# Connectors.net
KiCad netlist of a schematic drawn in Altium Designer
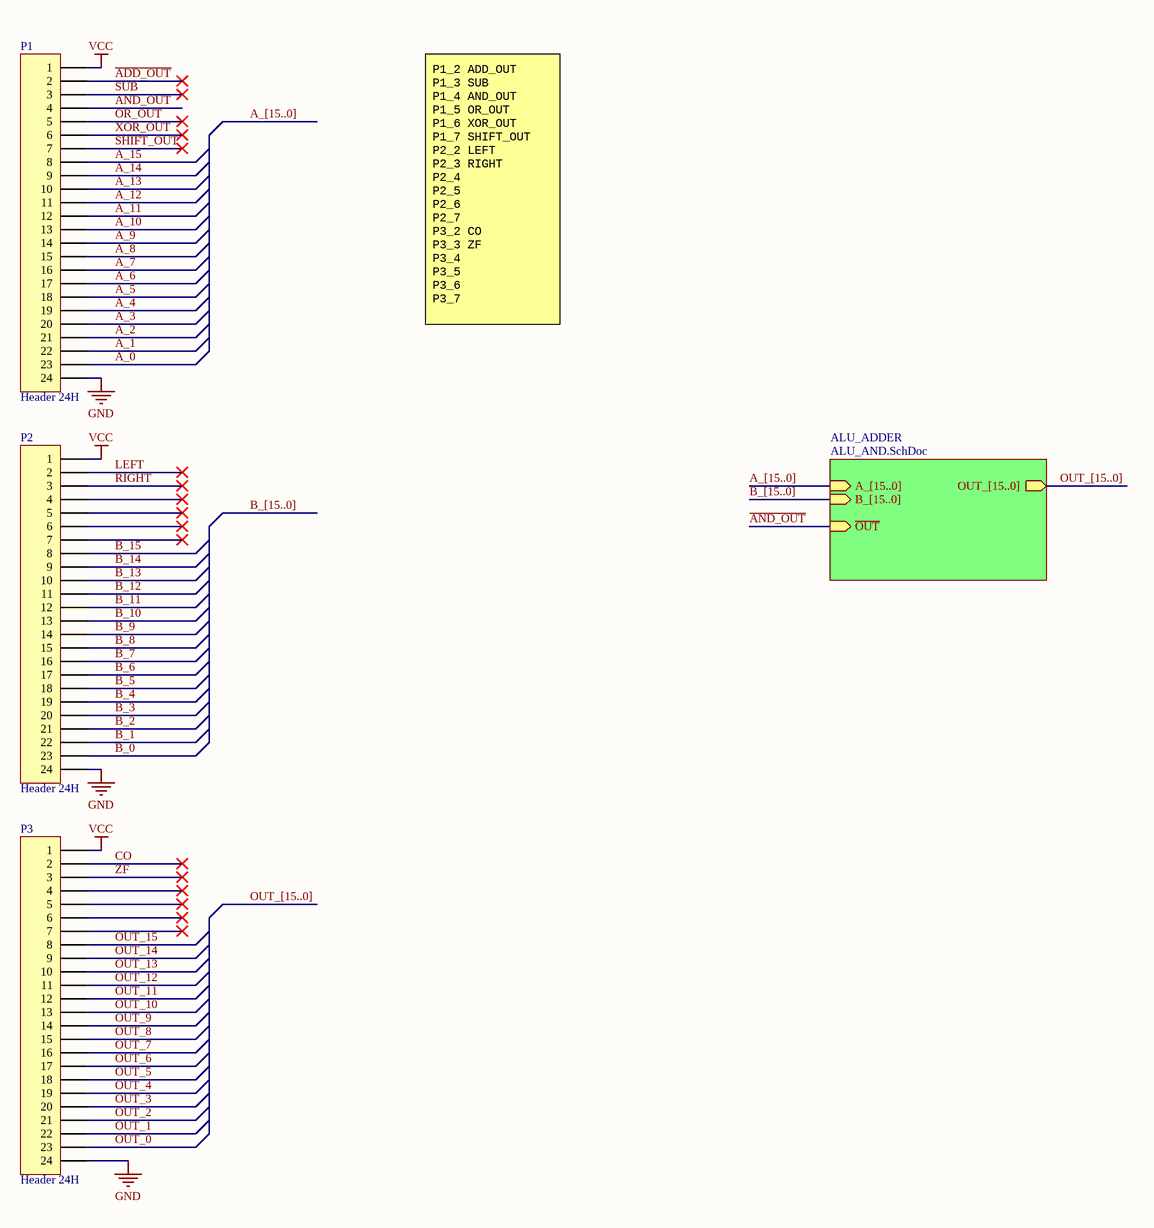
[diagram p0: Connectors.SchDoc]

(export (version "E")
  (design (tool "Eeschema 10.0.6"))
  (components
    (comp (ref "P1")
      (value "Header 24H")
      (footprint "HDR1X24H")
      (description "Header, 24-Pin, Right Angle")
      (fields (field (name "PUBLISHER") "Altium Limited"))
      (libsource (lib "Miscellaneous Connectors") (part "Header 24H"))
    )
    (comp (ref "P2")
      (value "Header 24H")
      (footprint "HDR1X24H")
      (description "Header, 24-Pin, Right Angle")
      (fields (field (name "PUBLISHER") "Altium Limited"))
      (libsource (lib "Miscellaneous Connectors") (part "Header 24H"))
    )
    (comp (ref "P3")
      (value "Header 24H")
      (footprint "HDR1X24H")
      (description "Header, 24-Pin, Right Angle")
      (fields (field (name "PUBLISHER") "Altium Limited"))
      (libsource (lib "Miscellaneous Connectors") (part "Header 24H"))
    )
  )
  (nets
    (net (code "1") (name "/A_0") (class "Default")
      (node (ref "P1") (pin "23") (pinfunction "23_23") (pintype "passive"))
    )
    (net (code "2") (name "/A_1") (class "Default")
      (node (ref "P1") (pin "22") (pinfunction "22_22") (pintype "passive"))
    )
    (net (code "3") (name "/A_2") (class "Default")
      (node (ref "P1") (pin "21") (pinfunction "21_21") (pintype "passive"))
    )
    (net (code "4") (name "/A_3") (class "Default")
      (node (ref "P1") (pin "20") (pinfunction "20_20") (pintype "passive"))
    )
    (net (code "5") (name "/A_4") (class "Default")
      (node (ref "P1") (pin "19") (pinfunction "19_19") (pintype "passive"))
    )
    (net (code "6") (name "/A_5") (class "Default")
      (node (ref "P1") (pin "18") (pinfunction "18_18") (pintype "passive"))
    )
    (net (code "7") (name "/A_6") (class "Default")
      (node (ref "P1") (pin "17") (pinfunction "17_17") (pintype "passive"))
    )
    (net (code "8") (name "/A_7") (class "Default")
      (node (ref "P1") (pin "16") (pinfunction "16_16") (pintype "passive"))
    )
    (net (code "9") (name "/A_8") (class "Default")
      (node (ref "P1") (pin "15") (pinfunction "15_15") (pintype "passive"))
    )
    (net (code "10") (name "/A_9") (class "Default")
      (node (ref "P1") (pin "14") (pinfunction "14_14") (pintype "passive"))
    )
    (net (code "11") (name "/A_10") (class "Default")
      (node (ref "P1") (pin "13") (pinfunction "13_13") (pintype "passive"))
    )
    (net (code "12") (name "/A_11") (class "Default")
      (node (ref "P1") (pin "12") (pinfunction "12_12") (pintype "passive"))
    )
    (net (code "13") (name "/A_12") (class "Default")
      (node (ref "P1") (pin "11") (pinfunction "11_11") (pintype "passive"))
    )
    (net (code "14") (name "/A_13") (class "Default")
      (node (ref "P1") (pin "10") (pinfunction "10_10") (pintype "passive"))
    )
    (net (code "15") (name "/A_14") (class "Default")
      (node (ref "P1") (pin "9") (pinfunction "9_9") (pintype "passive"))
    )
    (net (code "16") (name "/A_15") (class "Default")
      (node (ref "P1") (pin "8") (pinfunction "8_8") (pintype "passive"))
    )
    (net (code "18") (name "/B_0") (class "Default")
      (node (ref "P2") (pin "23") (pinfunction "23_23") (pintype "passive"))
    )
    (net (code "19") (name "/B_1") (class "Default")
      (node (ref "P2") (pin "22") (pinfunction "22_22") (pintype "passive"))
    )
    (net (code "20") (name "/B_2") (class "Default")
      (node (ref "P2") (pin "21") (pinfunction "21_21") (pintype "passive"))
    )
    (net (code "21") (name "/B_3") (class "Default")
      (node (ref "P2") (pin "20") (pinfunction "20_20") (pintype "passive"))
    )
    (net (code "22") (name "/B_4") (class "Default")
      (node (ref "P2") (pin "19") (pinfunction "19_19") (pintype "passive"))
    )
    (net (code "23") (name "/B_5") (class "Default")
      (node (ref "P2") (pin "18") (pinfunction "18_18") (pintype "passive"))
    )
    (net (code "24") (name "/B_6") (class "Default")
      (node (ref "P2") (pin "17") (pinfunction "17_17") (pintype "passive"))
    )
    (net (code "25") (name "/B_7") (class "Default")
      (node (ref "P2") (pin "16") (pinfunction "16_16") (pintype "passive"))
    )
    (net (code "26") (name "/B_8") (class "Default")
      (node (ref "P2") (pin "15") (pinfunction "15_15") (pintype "passive"))
    )
    (net (code "27") (name "/B_9") (class "Default")
      (node (ref "P2") (pin "14") (pinfunction "14_14") (pintype "passive"))
    )
    (net (code "28") (name "/B_10") (class "Default")
      (node (ref "P2") (pin "13") (pinfunction "13_13") (pintype "passive"))
    )
    (net (code "29") (name "/B_11") (class "Default")
      (node (ref "P2") (pin "12") (pinfunction "12_12") (pintype "passive"))
    )
    (net (code "30") (name "/B_12") (class "Default")
      (node (ref "P2") (pin "11") (pinfunction "11_11") (pintype "passive"))
    )
    (net (code "31") (name "/B_13") (class "Default")
      (node (ref "P2") (pin "10") (pinfunction "10_10") (pintype "passive"))
    )
    (net (code "32") (name "/B_14") (class "Default")
      (node (ref "P2") (pin "9") (pinfunction "9_9") (pintype "passive"))
    )
    (net (code "33") (name "/B_15") (class "Default")
      (node (ref "P2") (pin "8") (pinfunction "8_8") (pintype "passive"))
    )
    (net (code "35") (name "/CO") (class "Default")
      (node (ref "P3") (pin "2") (pinfunction "2_2") (pintype "passive+no_connect"))
    )
    (net (code "36") (name "/LEFT") (class "Default")
      (node (ref "P2") (pin "2") (pinfunction "2_2") (pintype "passive+no_connect"))
    )
    (net (code "37") (name "/OUT_0") (class "Default")
      (node (ref "P3") (pin "23") (pinfunction "23_23") (pintype "passive"))
    )
    (net (code "38") (name "/OUT_1") (class "Default")
      (node (ref "P3") (pin "22") (pinfunction "22_22") (pintype "passive"))
    )
    (net (code "39") (name "/OUT_2") (class "Default")
      (node (ref "P3") (pin "21") (pinfunction "21_21") (pintype "passive"))
    )
    (net (code "40") (name "/OUT_3") (class "Default")
      (node (ref "P3") (pin "20") (pinfunction "20_20") (pintype "passive"))
    )
    (net (code "41") (name "/OUT_4") (class "Default")
      (node (ref "P3") (pin "19") (pinfunction "19_19") (pintype "passive"))
    )
    (net (code "42") (name "/OUT_5") (class "Default")
      (node (ref "P3") (pin "18") (pinfunction "18_18") (pintype "passive"))
    )
    (net (code "43") (name "/OUT_6") (class "Default")
      (node (ref "P3") (pin "17") (pinfunction "17_17") (pintype "passive"))
    )
    (net (code "44") (name "/OUT_7") (class "Default")
      (node (ref "P3") (pin "16") (pinfunction "16_16") (pintype "passive"))
    )
    (net (code "45") (name "/OUT_8") (class "Default")
      (node (ref "P3") (pin "15") (pinfunction "15_15") (pintype "passive"))
    )
    (net (code "46") (name "/OUT_9") (class "Default")
      (node (ref "P3") (pin "14") (pinfunction "14_14") (pintype "passive"))
    )
    (net (code "47") (name "/OUT_10") (class "Default")
      (node (ref "P3") (pin "13") (pinfunction "13_13") (pintype "passive"))
    )
    (net (code "48") (name "/OUT_11") (class "Default")
      (node (ref "P3") (pin "12") (pinfunction "12_12") (pintype "passive"))
    )
    (net (code "49") (name "/OUT_12") (class "Default")
      (node (ref "P3") (pin "11") (pinfunction "11_11") (pintype "passive"))
    )
    (net (code "50") (name "/OUT_13") (class "Default")
      (node (ref "P3") (pin "10") (pinfunction "10_10") (pintype "passive"))
    )
    (net (code "51") (name "/OUT_14") (class "Default")
      (node (ref "P3") (pin "9") (pinfunction "9_9") (pintype "passive"))
    )
    (net (code "52") (name "/OUT_15") (class "Default")
      (node (ref "P3") (pin "8") (pinfunction "8_8") (pintype "passive"))
    )
    (net (code "54") (name "/RIGHT") (class "Default")
      (node (ref "P2") (pin "3") (pinfunction "3_3") (pintype "passive+no_connect"))
    )
    (net (code "55") (name "/SUB") (class "Default")
      (node (ref "P1") (pin "3") (pinfunction "3_3") (pintype "passive+no_connect"))
    )
    (net (code "56") (name "/~{ADD_OUT}") (class "Default")
      (node (ref "P1") (pin "2") (pinfunction "2_2") (pintype "passive+no_connect"))
    )
    (net (code "57") (name "/~{AND_OUT}") (class "Default")
      (node (ref "P1") (pin "4") (pinfunction "4_4") (pintype "passive"))
    )
    (net (code "58") (name "/~{OR_OUT}") (class "Default")
      (node (ref "P1") (pin "5") (pinfunction "5_5") (pintype "passive+no_connect"))
    )
    (net (code "59") (name "/~{SHIFT_OUT}") (class "Default")
      (node (ref "P1") (pin "7") (pinfunction "7_7") (pintype "passive+no_connect"))
    )
    (net (code "60") (name "/~{XOR_OUT}") (class "Default")
      (node (ref "P1") (pin "6") (pinfunction "6_6") (pintype "passive+no_connect"))
    )
    (net (code "61") (name "/~{ZF}") (class "Default")
      (node (ref "P3") (pin "3") (pinfunction "3_3") (pintype "passive+no_connect"))
    )
    (net (code "62") (name "GND") (class "Default")
      (node (ref "P1") (pin "24") (pinfunction "24_24") (pintype "passive"))
      (node (ref "P2") (pin "24") (pinfunction "24_24") (pintype "passive"))
      (node (ref "P3") (pin "24") (pinfunction "24_24") (pintype "passive"))
    )
    (net (code "63") (name "VCC") (class "Default")
      (node (ref "P1") (pin "1") (pinfunction "1_1") (pintype "passive"))
      (node (ref "P2") (pin "1") (pinfunction "1_1") (pintype "passive"))
      (node (ref "P3") (pin "1") (pinfunction "1_1") (pintype "passive"))
    )
    (net (code "64") (name "unconnected-(P2-Pad4)") (class "Default")
      (node (ref "P2") (pin "4") (pinfunction "4_4") (pintype "passive+no_connect"))
    )
    (net (code "65") (name "unconnected-(P2-Pad5)") (class "Default")
      (node (ref "P2") (pin "5") (pinfunction "5_5") (pintype "passive+no_connect"))
    )
    (net (code "66") (name "unconnected-(P2-Pad6)") (class "Default")
      (node (ref "P2") (pin "6") (pinfunction "6_6") (pintype "passive+no_connect"))
    )
    (net (code "67") (name "unconnected-(P2-Pad7)") (class "Default")
      (node (ref "P2") (pin "7") (pinfunction "7_7") (pintype "passive+no_connect"))
    )
    (net (code "68") (name "unconnected-(P3-Pad4)") (class "Default")
      (node (ref "P3") (pin "4") (pinfunction "4_4") (pintype "passive+no_connect"))
    )
    (net (code "69") (name "unconnected-(P3-Pad5)") (class "Default")
      (node (ref "P3") (pin "5") (pinfunction "5_5") (pintype "passive+no_connect"))
    )
    (net (code "70") (name "unconnected-(P3-Pad6)") (class "Default")
      (node (ref "P3") (pin "6") (pinfunction "6_6") (pintype "passive+no_connect"))
    )
    (net (code "71") (name "unconnected-(P3-Pad7)") (class "Default")
      (node (ref "P3") (pin "7") (pinfunction "7_7") (pintype "passive+no_connect"))
    )
  )
)
